# TLNS_driver_board.net
KiCad netlist of a schematic drawn in EAGLE
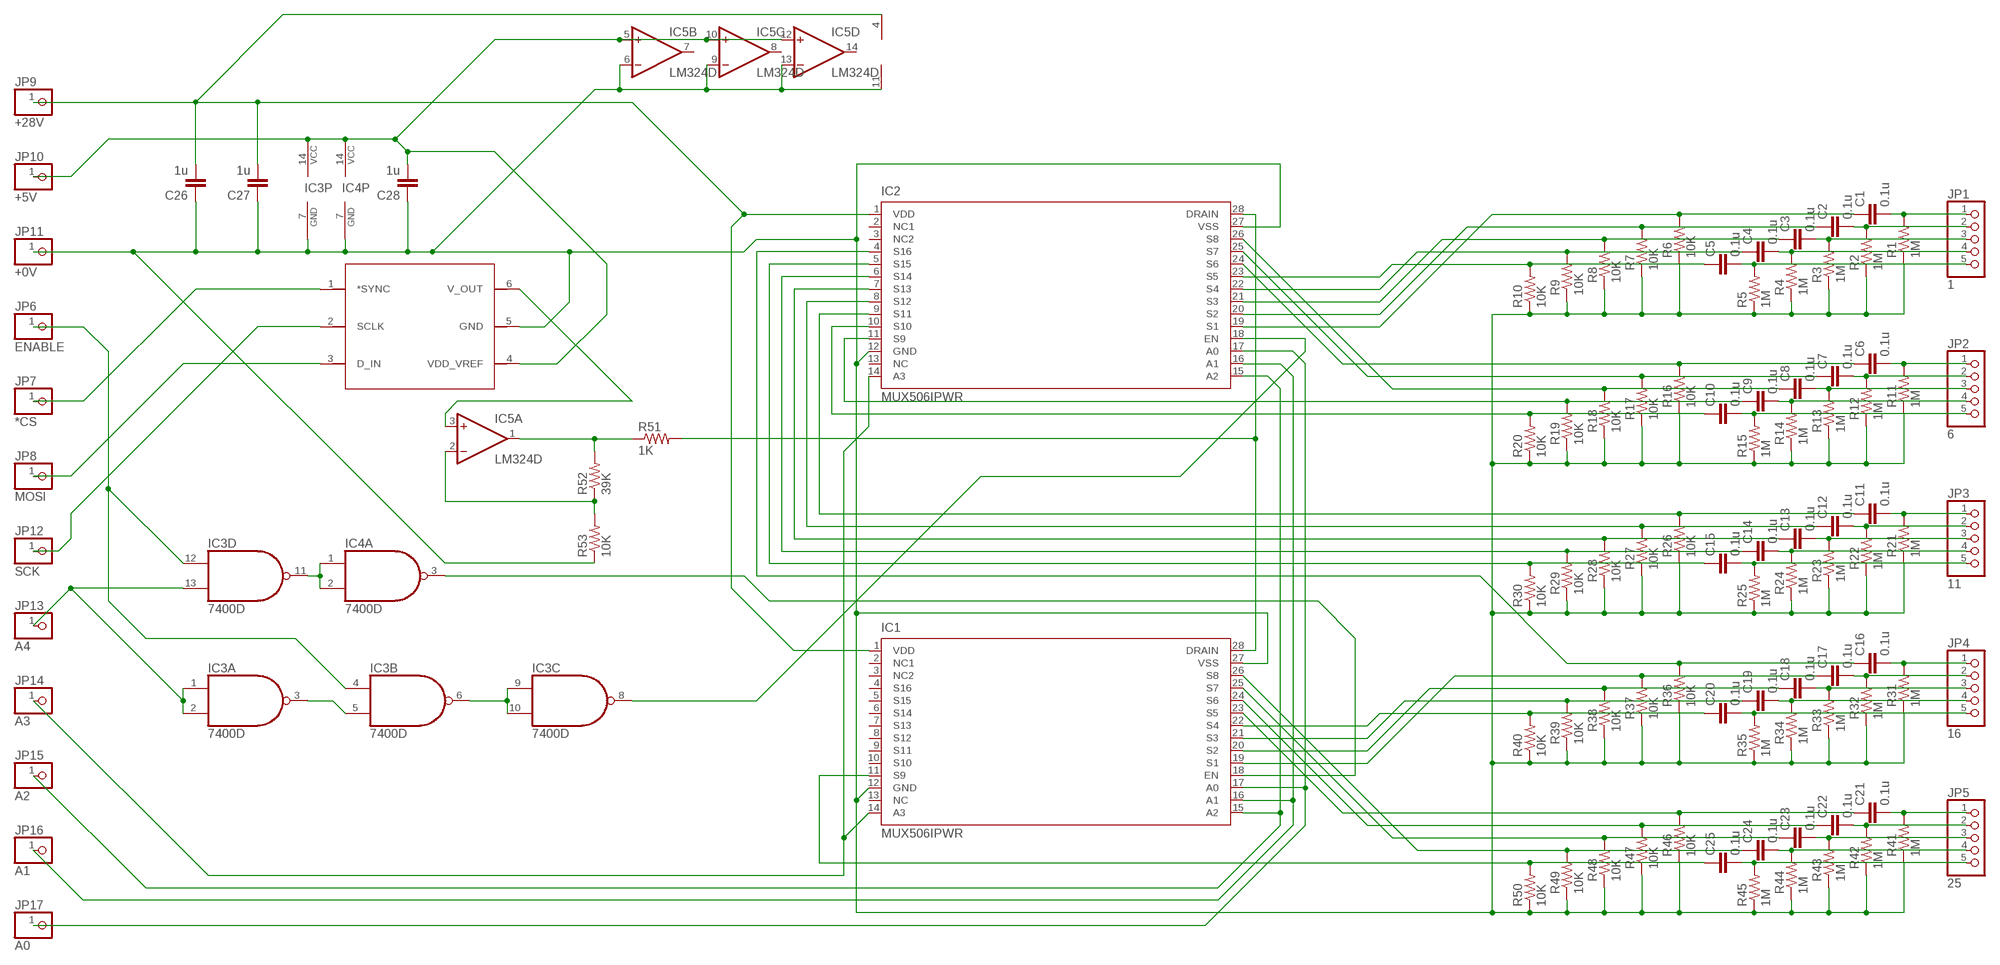
[diagram p0: schematic, sheet 1]

(export (version "E")
  (design (tool "Eeschema 10.0.6"))
  (components
    (comp (ref "C1")
      (value "0.1u")
      (footprint "eagle-import:C0603K")
      (libsource (lib "eagle-import") (part "C-EUC0603K"))
    )
    (comp (ref "C2")
      (value "0.1u")
      (footprint "eagle-import:C0603K")
      (libsource (lib "eagle-import") (part "C-EUC0603K"))
    )
    (comp (ref "C3")
      (value "0.1u")
      (footprint "eagle-import:C0603K")
      (libsource (lib "eagle-import") (part "C-EUC0603K"))
    )
    (comp (ref "C4")
      (value "0.1u")
      (footprint "eagle-import:C0603K")
      (libsource (lib "eagle-import") (part "C-EUC0603K"))
    )
    (comp (ref "C5")
      (value "0.1u")
      (footprint "eagle-import:C0603K")
      (libsource (lib "eagle-import") (part "C-EUC0603K"))
    )
    (comp (ref "C6")
      (value "0.1u")
      (footprint "eagle-import:C0603K")
      (libsource (lib "eagle-import") (part "C-EUC0603K"))
    )
    (comp (ref "C7")
      (value "0.1u")
      (footprint "eagle-import:C0603K")
      (libsource (lib "eagle-import") (part "C-EUC0603K"))
    )
    (comp (ref "C8")
      (value "0.1u")
      (footprint "eagle-import:C0603K")
      (libsource (lib "eagle-import") (part "C-EUC0603K"))
    )
    (comp (ref "C9")
      (value "0.1u")
      (footprint "eagle-import:C0603K")
      (libsource (lib "eagle-import") (part "C-EUC0603K"))
    )
    (comp (ref "C10")
      (value "0.1u")
      (footprint "eagle-import:C0603K")
      (libsource (lib "eagle-import") (part "C-EUC0603K"))
    )
    (comp (ref "C11")
      (value "0.1u")
      (footprint "eagle-import:C0603K")
      (libsource (lib "eagle-import") (part "C-EUC0603K"))
    )
    (comp (ref "C12")
      (value "0.1u")
      (footprint "eagle-import:C0603K")
      (libsource (lib "eagle-import") (part "C-EUC0603K"))
    )
    (comp (ref "C13")
      (value "0.1u")
      (footprint "eagle-import:C0603K")
      (libsource (lib "eagle-import") (part "C-EUC0603K"))
    )
    (comp (ref "C14")
      (value "0.1u")
      (footprint "eagle-import:C0603K")
      (libsource (lib "eagle-import") (part "C-EUC0603K"))
    )
    (comp (ref "C15")
      (value "0.1u")
      (footprint "eagle-import:C0603K")
      (libsource (lib "eagle-import") (part "C-EUC0603K"))
    )
    (comp (ref "C16")
      (value "0.1u")
      (footprint "eagle-import:C0603K")
      (libsource (lib "eagle-import") (part "C-EUC0603K"))
    )
    (comp (ref "C17")
      (value "0.1u")
      (footprint "eagle-import:C0603K")
      (libsource (lib "eagle-import") (part "C-EUC0603K"))
    )
    (comp (ref "C18")
      (value "0.1u")
      (footprint "eagle-import:C0603K")
      (libsource (lib "eagle-import") (part "C-EUC0603K"))
    )
    (comp (ref "C19")
      (value "0.1u")
      (footprint "eagle-import:C0603K")
      (libsource (lib "eagle-import") (part "C-EUC0603K"))
    )
    (comp (ref "C20")
      (value "0.1u")
      (footprint "eagle-import:C0603K")
      (libsource (lib "eagle-import") (part "C-EUC0603K"))
    )
    (comp (ref "C21")
      (value "0.1u")
      (footprint "eagle-import:C0603K")
      (libsource (lib "eagle-import") (part "C-EUC0603K"))
    )
    (comp (ref "C22")
      (value "0.1u")
      (footprint "eagle-import:C0603K")
      (libsource (lib "eagle-import") (part "C-EUC0603K"))
    )
    (comp (ref "C23")
      (value "0.1u")
      (footprint "eagle-import:C0603K")
      (libsource (lib "eagle-import") (part "C-EUC0603K"))
    )
    (comp (ref "C24")
      (value "0.1u")
      (footprint "eagle-import:C0603K")
      (libsource (lib "eagle-import") (part "C-EUC0603K"))
    )
    (comp (ref "C25")
      (value "0.1u")
      (footprint "eagle-import:C0603K")
      (libsource (lib "eagle-import") (part "C-EUC0603K"))
    )
    (comp (ref "C26")
      (value "1u")
      (footprint "eagle-import:C0603K")
      (libsource (lib "eagle-import") (part "C-EUC0603K"))
    )
    (comp (ref "C27")
      (value "1u")
      (footprint "eagle-import:C0603K")
      (libsource (lib "eagle-import") (part "C-EUC0603K"))
    )
    (comp (ref "C28")
      (value "1u")
      (footprint "eagle-import:C0603K")
      (libsource (lib "eagle-import") (part "C-EUC0603K"))
    )
    (comp (ref "IC1")
      (value "MUX506IPWR")
      (footprint "eagle-import:SO28W")
      (fields (field (name "MF") "MICROCHIP") (field (name "MPN") "PIC18F2550-I/SO"))
      (libsource (lib "eagle-import") (part "MUX506IPWRW550"))
    )
    (comp (ref "IC2")
      (value "MUX506IPWR")
      (footprint "eagle-import:SO28W")
      (fields (field (name "MF") "MICROCHIP") (field (name "MPN") "PIC18F2550-I/SO"))
      (libsource (lib "eagle-import") (part "MUX506IPWRW550"))
    )
    (comp (ref "IC3")
      (value "7400D")
      (footprint "eagle-import:SO14")
      (libsource (lib "eagle-import") (part "7400D"))
    )
    (comp (ref "IC4")
      (value "7400D")
      (footprint "eagle-import:SO14")
      (libsource (lib "eagle-import") (part "7400D"))
    )
    (comp (ref "IC5")
      (value "LM324D")
      (footprint "eagle-import:SO14")
      (libsource (lib "eagle-import") (part "LM324D"))
    )
    (comp (ref "JP1")
      (value "1")
      (footprint "eagle-import:1X05")
      (libsource (lib "eagle-import") (part "PINHD-1X5"))
    )
    (comp (ref "JP2")
      (value "6")
      (footprint "eagle-import:1X05")
      (libsource (lib "eagle-import") (part "PINHD-1X5"))
    )
    (comp (ref "JP3")
      (value "11")
      (footprint "eagle-import:1X05")
      (libsource (lib "eagle-import") (part "PINHD-1X5"))
    )
    (comp (ref "JP4")
      (value "16")
      (footprint "eagle-import:1X05")
      (libsource (lib "eagle-import") (part "PINHD-1X5"))
    )
    (comp (ref "JP5")
      (value "25")
      (footprint "eagle-import:1X05")
      (libsource (lib "eagle-import") (part "PINHD-1X5"))
    )
    (comp (ref "JP6")
      (value "ENABLE")
      (footprint "eagle-import:1X01")
      (libsource (lib "eagle-import") (part "PINHD-1X1"))
    )
    (comp (ref "JP7")
      (value "*CS")
      (footprint "eagle-import:1X01")
      (libsource (lib "eagle-import") (part "PINHD-1X1"))
    )
    (comp (ref "JP8")
      (value "MOSI")
      (footprint "eagle-import:1X01")
      (libsource (lib "eagle-import") (part "PINHD-1X1"))
    )
    (comp (ref "JP9")
      (value "+28V")
      (footprint "eagle-import:1X01")
      (libsource (lib "eagle-import") (part "PINHD-1X1"))
    )
    (comp (ref "JP10")
      (value "+5V")
      (footprint "eagle-import:1X01")
      (libsource (lib "eagle-import") (part "PINHD-1X1"))
    )
    (comp (ref "JP11")
      (value "+0V")
      (footprint "eagle-import:1X01")
      (libsource (lib "eagle-import") (part "PINHD-1X1"))
    )
    (comp (ref "JP12")
      (value "SCK")
      (footprint "eagle-import:1X01")
      (libsource (lib "eagle-import") (part "PINHD-1X1"))
    )
    (comp (ref "JP13")
      (value "A4")
      (footprint "eagle-import:1X01")
      (libsource (lib "eagle-import") (part "PINHD-1X1"))
    )
    (comp (ref "JP14")
      (value "A3")
      (footprint "eagle-import:1X01")
      (libsource (lib "eagle-import") (part "PINHD-1X1"))
    )
    (comp (ref "JP15")
      (value "A2")
      (footprint "eagle-import:1X01")
      (libsource (lib "eagle-import") (part "PINHD-1X1"))
    )
    (comp (ref "JP16")
      (value "A1")
      (footprint "eagle-import:1X01")
      (libsource (lib "eagle-import") (part "PINHD-1X1"))
    )
    (comp (ref "JP17")
      (value "A0")
      (footprint "eagle-import:1X01")
      (libsource (lib "eagle-import") (part "PINHD-1X1"))
    )
    (comp (ref "R1")
      (value "1M")
      (footprint "eagle-import:R0603")
      (libsource (lib "eagle-import") (part "R-US_R0603"))
    )
    (comp (ref "R2")
      (value "1M")
      (footprint "eagle-import:R0603")
      (libsource (lib "eagle-import") (part "R-US_R0603"))
    )
    (comp (ref "R3")
      (value "1M")
      (footprint "eagle-import:R0603")
      (libsource (lib "eagle-import") (part "R-US_R0603"))
    )
    (comp (ref "R4")
      (value "1M")
      (footprint "eagle-import:R0603")
      (libsource (lib "eagle-import") (part "R-US_R0603"))
    )
    (comp (ref "R5")
      (value "1M")
      (footprint "eagle-import:R0603")
      (libsource (lib "eagle-import") (part "R-US_R0603"))
    )
    (comp (ref "R6")
      (value "10K")
      (footprint "eagle-import:R0603")
      (libsource (lib "eagle-import") (part "R-US_R0603"))
    )
    (comp (ref "R7")
      (value "10K")
      (footprint "eagle-import:R0603")
      (libsource (lib "eagle-import") (part "R-US_R0603"))
    )
    (comp (ref "R8")
      (value "10K")
      (footprint "eagle-import:R0603")
      (libsource (lib "eagle-import") (part "R-US_R0603"))
    )
    (comp (ref "R9")
      (value "10K")
      (footprint "eagle-import:R0603")
      (libsource (lib "eagle-import") (part "R-US_R0603"))
    )
    (comp (ref "R10")
      (value "10K")
      (footprint "eagle-import:R0603")
      (libsource (lib "eagle-import") (part "R-US_R0603"))
    )
    (comp (ref "R11")
      (value "1M")
      (footprint "eagle-import:R0603")
      (libsource (lib "eagle-import") (part "R-US_R0603"))
    )
    (comp (ref "R12")
      (value "1M")
      (footprint "eagle-import:R0603")
      (libsource (lib "eagle-import") (part "R-US_R0603"))
    )
    (comp (ref "R13")
      (value "1M")
      (footprint "eagle-import:R0603")
      (libsource (lib "eagle-import") (part "R-US_R0603"))
    )
    (comp (ref "R14")
      (value "1M")
      (footprint "eagle-import:R0603")
      (libsource (lib "eagle-import") (part "R-US_R0603"))
    )
    (comp (ref "R15")
      (value "1M")
      (footprint "eagle-import:R0603")
      (libsource (lib "eagle-import") (part "R-US_R0603"))
    )
    (comp (ref "R16")
      (value "10K")
      (footprint "eagle-import:R0603")
      (libsource (lib "eagle-import") (part "R-US_R0603"))
    )
    (comp (ref "R17")
      (value "10K")
      (footprint "eagle-import:R0603")
      (libsource (lib "eagle-import") (part "R-US_R0603"))
    )
    (comp (ref "R18")
      (value "10K")
      (footprint "eagle-import:R0603")
      (libsource (lib "eagle-import") (part "R-US_R0603"))
    )
    (comp (ref "R19")
      (value "10K")
      (footprint "eagle-import:R0603")
      (libsource (lib "eagle-import") (part "R-US_R0603"))
    )
    (comp (ref "R20")
      (value "10K")
      (footprint "eagle-import:R0603")
      (libsource (lib "eagle-import") (part "R-US_R0603"))
    )
    (comp (ref "R21")
      (value "1M")
      (footprint "eagle-import:R0603")
      (libsource (lib "eagle-import") (part "R-US_R0603"))
    )
    (comp (ref "R22")
      (value "1M")
      (footprint "eagle-import:R0603")
      (libsource (lib "eagle-import") (part "R-US_R0603"))
    )
    (comp (ref "R23")
      (value "1M")
      (footprint "eagle-import:R0603")
      (libsource (lib "eagle-import") (part "R-US_R0603"))
    )
    (comp (ref "R24")
      (value "1M")
      (footprint "eagle-import:R0603")
      (libsource (lib "eagle-import") (part "R-US_R0603"))
    )
    (comp (ref "R25")
      (value "1M")
      (footprint "eagle-import:R0603")
      (libsource (lib "eagle-import") (part "R-US_R0603"))
    )
    (comp (ref "R26")
      (value "10K")
      (footprint "eagle-import:R0603")
      (libsource (lib "eagle-import") (part "R-US_R0603"))
    )
    (comp (ref "R27")
      (value "10K")
      (footprint "eagle-import:R0603")
      (libsource (lib "eagle-import") (part "R-US_R0603"))
    )
    (comp (ref "R28")
      (value "10K")
      (footprint "eagle-import:R0603")
      (libsource (lib "eagle-import") (part "R-US_R0603"))
    )
    (comp (ref "R29")
      (value "10K")
      (footprint "eagle-import:R0603")
      (libsource (lib "eagle-import") (part "R-US_R0603"))
    )
    (comp (ref "R30")
      (value "10K")
      (footprint "eagle-import:R0603")
      (libsource (lib "eagle-import") (part "R-US_R0603"))
    )
    (comp (ref "R31")
      (value "1M")
      (footprint "eagle-import:R0603")
      (libsource (lib "eagle-import") (part "R-US_R0603"))
    )
    (comp (ref "R32")
      (value "1M")
      (footprint "eagle-import:R0603")
      (libsource (lib "eagle-import") (part "R-US_R0603"))
    )
    (comp (ref "R33")
      (value "1M")
      (footprint "eagle-import:R0603")
      (libsource (lib "eagle-import") (part "R-US_R0603"))
    )
    (comp (ref "R34")
      (value "1M")
      (footprint "eagle-import:R0603")
      (libsource (lib "eagle-import") (part "R-US_R0603"))
    )
    (comp (ref "R35")
      (value "1M")
      (footprint "eagle-import:R0603")
      (libsource (lib "eagle-import") (part "R-US_R0603"))
    )
    (comp (ref "R36")
      (value "10K")
      (footprint "eagle-import:R0603")
      (libsource (lib "eagle-import") (part "R-US_R0603"))
    )
    (comp (ref "R37")
      (value "10K")
      (footprint "eagle-import:R0603")
      (libsource (lib "eagle-import") (part "R-US_R0603"))
    )
    (comp (ref "R38")
      (value "10K")
      (footprint "eagle-import:R0603")
      (libsource (lib "eagle-import") (part "R-US_R0603"))
    )
    (comp (ref "R39")
      (value "10K")
      (footprint "eagle-import:R0603")
      (libsource (lib "eagle-import") (part "R-US_R0603"))
    )
    (comp (ref "R40")
      (value "10K")
      (footprint "eagle-import:R0603")
      (libsource (lib "eagle-import") (part "R-US_R0603"))
    )
    (comp (ref "R41")
      (value "1M")
      (footprint "eagle-import:R0603")
      (libsource (lib "eagle-import") (part "R-US_R0603"))
    )
    (comp (ref "R42")
      (value "1M")
      (footprint "eagle-import:R0603")
      (libsource (lib "eagle-import") (part "R-US_R0603"))
    )
    (comp (ref "R43")
      (value "1M")
      (footprint "eagle-import:R0603")
      (libsource (lib "eagle-import") (part "R-US_R0603"))
    )
    (comp (ref "R44")
      (value "1M")
      (footprint "eagle-import:R0603")
      (libsource (lib "eagle-import") (part "R-US_R0603"))
    )
    (comp (ref "R45")
      (value "1M")
      (footprint "eagle-import:R0603")
      (libsource (lib "eagle-import") (part "R-US_R0603"))
    )
    (comp (ref "R46")
      (value "10K")
      (footprint "eagle-import:R0603")
      (libsource (lib "eagle-import") (part "R-US_R0603"))
    )
    (comp (ref "R47")
      (value "10K")
      (footprint "eagle-import:R0603")
      (libsource (lib "eagle-import") (part "R-US_R0603"))
    )
    (comp (ref "R48")
      (value "10K")
      (footprint "eagle-import:R0603")
      (libsource (lib "eagle-import") (part "R-US_R0603"))
    )
    (comp (ref "R49")
      (value "10K")
      (footprint "eagle-import:R0603")
      (libsource (lib "eagle-import") (part "R-US_R0603"))
    )
    (comp (ref "R50")
      (value "10K")
      (footprint "eagle-import:R0603")
      (libsource (lib "eagle-import") (part "R-US_R0603"))
    )
    (comp (ref "R51")
      (value "1K")
      (footprint "eagle-import:R1206")
      (libsource (lib "eagle-import") (part "R-US_R1206"))
    )
    (comp (ref "R52")
      (value "39K")
      (footprint "eagle-import:R0603")
      (libsource (lib "eagle-import") (part "R-US_R0603"))
    )
    (comp (ref "R53")
      (value "10K")
      (footprint "eagle-import:R0603")
      (libsource (lib "eagle-import") (part "R-US_R0603"))
    )
    (comp (ref "U$1")
      (value "DAC7311")
      (footprint "eagle-import:SC70-6")
      (libsource (lib "eagle-import") (part "DAC7311"))
    )
  )
  (nets
    (net (code "1") (name "/S12") (class "Default")
      (node (ref "IC1") (pin "8") (pinfunction "S12_8") (pintype "power_in"))
    )
    (net (code "2") (name "Net-(C1-Pad2)") (class "Default")
      (node (ref "C1") (pin "2") (pinfunction "2_2") (pintype "passive"))
      (node (ref "JP1") (pin "1") (pinfunction "1_1") (pintype "passive"))
      (node (ref "R1") (pin "2") (pinfunction "2_2") (pintype "passive"))
    )
    (net (code "3") (name "Net-(C2-Pad2)") (class "Default")
      (node (ref "C2") (pin "2") (pinfunction "2_2") (pintype "passive"))
      (node (ref "JP1") (pin "2") (pinfunction "2_2") (pintype "passive"))
      (node (ref "R2") (pin "2") (pinfunction "2_2") (pintype "passive"))
    )
    (net (code "4") (name "Net-(C3-Pad2)") (class "Default")
      (node (ref "C3") (pin "2") (pinfunction "2_2") (pintype "passive"))
      (node (ref "JP1") (pin "3") (pinfunction "3_3") (pintype "passive"))
      (node (ref "R3") (pin "2") (pinfunction "2_2") (pintype "passive"))
    )
    (net (code "5") (name "Net-(C4-Pad2)") (class "Default")
      (node (ref "C4") (pin "2") (pinfunction "2_2") (pintype "passive"))
      (node (ref "JP1") (pin "4") (pinfunction "4_4") (pintype "passive"))
      (node (ref "R4") (pin "2") (pinfunction "2_2") (pintype "passive"))
    )
    (net (code "6") (name "Net-(C5-Pad2)") (class "Default")
      (node (ref "C5") (pin "2") (pinfunction "2_2") (pintype "passive"))
      (node (ref "JP1") (pin "5") (pinfunction "5_5") (pintype "passive"))
      (node (ref "R5") (pin "2") (pinfunction "2_2") (pintype "passive"))
    )
    (net (code "7") (name "Net-(C6-Pad2)") (class "Default")
      (node (ref "C6") (pin "2") (pinfunction "2_2") (pintype "passive"))
      (node (ref "JP2") (pin "1") (pinfunction "1_1") (pintype "passive"))
      (node (ref "R11") (pin "2") (pinfunction "2_2") (pintype "passive"))
    )
    (net (code "8") (name "Net-(C7-Pad2)") (class "Default")
      (node (ref "C7") (pin "2") (pinfunction "2_2") (pintype "passive"))
      (node (ref "JP2") (pin "2") (pinfunction "2_2") (pintype "passive"))
      (node (ref "R12") (pin "2") (pinfunction "2_2") (pintype "passive"))
    )
    (net (code "9") (name "Net-(C8-Pad2)") (class "Default")
      (node (ref "C8") (pin "2") (pinfunction "2_2") (pintype "passive"))
      (node (ref "JP2") (pin "3") (pinfunction "3_3") (pintype "passive"))
      (node (ref "R13") (pin "2") (pinfunction "2_2") (pintype "passive"))
    )
    (net (code "10") (name "Net-(C9-Pad2)") (class "Default")
      (node (ref "C9") (pin "2") (pinfunction "2_2") (pintype "passive"))
      (node (ref "JP2") (pin "4") (pinfunction "4_4") (pintype "passive"))
      (node (ref "R14") (pin "2") (pinfunction "2_2") (pintype "passive"))
    )
    (net (code "11") (name "Net-(C10-Pad2)") (class "Default")
      (node (ref "C10") (pin "2") (pinfunction "2_2") (pintype "passive"))
      (node (ref "JP2") (pin "5") (pinfunction "5_5") (pintype "passive"))
      (node (ref "R15") (pin "2") (pinfunction "2_2") (pintype "passive"))
    )
    (net (code "12") (name "Net-(C11-Pad2)") (class "Default")
      (node (ref "C11") (pin "2") (pinfunction "2_2") (pintype "passive"))
      (node (ref "JP3") (pin "1") (pinfunction "1_1") (pintype "passive"))
      (node (ref "R21") (pin "2") (pinfunction "2_2") (pintype "passive"))
    )
    (net (code "13") (name "Net-(C12-Pad2)") (class "Default")
      (node (ref "C12") (pin "2") (pinfunction "2_2") (pintype "passive"))
      (node (ref "JP3") (pin "2") (pinfunction "2_2") (pintype "passive"))
      (node (ref "R22") (pin "2") (pinfunction "2_2") (pintype "passive"))
    )
    (net (code "14") (name "Net-(C13-Pad2)") (class "Default")
      (node (ref "C13") (pin "2") (pinfunction "2_2") (pintype "passive"))
      (node (ref "JP3") (pin "3") (pinfunction "3_3") (pintype "passive"))
      (node (ref "R23") (pin "2") (pinfunction "2_2") (pintype "passive"))
    )
    (net (code "15") (name "Net-(C14-Pad2)") (class "Default")
      (node (ref "C14") (pin "2") (pinfunction "2_2") (pintype "passive"))
      (node (ref "JP3") (pin "4") (pinfunction "4_4") (pintype "passive"))
      (node (ref "R24") (pin "2") (pinfunction "2_2") (pintype "passive"))
    )
    (net (code "16") (name "Net-(C15-Pad2)") (class "Default")
      (node (ref "C15") (pin "2") (pinfunction "2_2") (pintype "passive"))
      (node (ref "JP3") (pin "5") (pinfunction "5_5") (pintype "passive"))
      (node (ref "R25") (pin "2") (pinfunction "2_2") (pintype "passive"))
    )
    (net (code "17") (name "Net-(C16-Pad2)") (class "Default")
      (node (ref "C16") (pin "2") (pinfunction "2_2") (pintype "passive"))
      (node (ref "JP4") (pin "1") (pinfunction "1_1") (pintype "passive"))
      (node (ref "R31") (pin "2") (pinfunction "2_2") (pintype "passive"))
    )
    (net (code "18") (name "Net-(C17-Pad2)") (class "Default")
      (node (ref "C17") (pin "2") (pinfunction "2_2") (pintype "passive"))
      (node (ref "JP4") (pin "2") (pinfunction "2_2") (pintype "passive"))
      (node (ref "R32") (pin "2") (pinfunction "2_2") (pintype "passive"))
    )
    (net (code "19") (name "Net-(C18-Pad2)") (class "Default")
      (node (ref "C18") (pin "2") (pinfunction "2_2") (pintype "passive"))
      (node (ref "JP4") (pin "3") (pinfunction "3_3") (pintype "passive"))
      (node (ref "R33") (pin "2") (pinfunction "2_2") (pintype "passive"))
    )
    (net (code "20") (name "Net-(C19-Pad2)") (class "Default")
      (node (ref "C19") (pin "2") (pinfunction "2_2") (pintype "passive"))
      (node (ref "JP4") (pin "4") (pinfunction "4_4") (pintype "passive"))
      (node (ref "R34") (pin "2") (pinfunction "2_2") (pintype "passive"))
    )
    (net (code "21") (name "Net-(C20-Pad2)") (class "Default")
      (node (ref "C20") (pin "2") (pinfunction "2_2") (pintype "passive"))
      (node (ref "JP4") (pin "5") (pinfunction "5_5") (pintype "passive"))
      (node (ref "R35") (pin "2") (pinfunction "2_2") (pintype "passive"))
    )
    (net (code "22") (name "Net-(C21-Pad2)") (class "Default")
      (node (ref "C21") (pin "2") (pinfunction "2_2") (pintype "passive"))
      (node (ref "JP5") (pin "1") (pinfunction "1_1") (pintype "passive"))
      (node (ref "R41") (pin "2") (pinfunction "2_2") (pintype "passive"))
    )
    (net (code "23") (name "Net-(C22-Pad2)") (class "Default")
      (node (ref "C22") (pin "2") (pinfunction "2_2") (pintype "passive"))
      (node (ref "JP5") (pin "2") (pinfunction "2_2") (pintype "passive"))
      (node (ref "R42") (pin "2") (pinfunction "2_2") (pintype "passive"))
    )
    (net (code "24") (name "Net-(C23-Pad2)") (class "Default")
      (node (ref "C23") (pin "2") (pinfunction "2_2") (pintype "passive"))
      (node (ref "JP5") (pin "3") (pinfunction "3_3") (pintype "passive"))
      (node (ref "R43") (pin "2") (pinfunction "2_2") (pintype "passive"))
    )
    (net (code "25") (name "Net-(C24-Pad2)") (class "Default")
      (node (ref "C24") (pin "2") (pinfunction "2_2") (pintype "passive"))
      (node (ref "JP5") (pin "4") (pinfunction "4_4") (pintype "passive"))
      (node (ref "R44") (pin "2") (pinfunction "2_2") (pintype "passive"))
    )
    (net (code "26") (name "Net-(C25-Pad2)") (class "Default")
      (node (ref "C25") (pin "2") (pinfunction "2_2") (pintype "passive"))
      (node (ref "JP5") (pin "5") (pinfunction "5_5") (pintype "passive"))
      (node (ref "R45") (pin "2") (pinfunction "2_2") (pintype "passive"))
    )
    (net (code "27") (name "Net-(IC1-A0)") (class "Default")
      (node (ref "IC1") (pin "17") (pinfunction "A0_17") (pintype "bidirectional"))
      (node (ref "IC2") (pin "17") (pinfunction "A0_17") (pintype "bidirectional"))
      (node (ref "JP17") (pin "1") (pinfunction "1_1") (pintype "passive"))
    )
    (net (code "28") (name "Net-(IC1-A1)") (class "Default")
      (node (ref "IC1") (pin "16") (pinfunction "A1_16") (pintype "bidirectional"))
      (node (ref "IC2") (pin "16") (pinfunction "A1_16") (pintype "bidirectional"))
      (node (ref "JP16") (pin "1") (pinfunction "1_1") (pintype "passive"))
    )
    (net (code "29") (name "Net-(IC1-A2)") (class "Default")
      (node (ref "IC1") (pin "15") (pinfunction "A2_15") (pintype "bidirectional"))
      (node (ref "IC2") (pin "15") (pinfunction "A2_15") (pintype "bidirectional"))
      (node (ref "JP15") (pin "1") (pinfunction "1_1") (pintype "passive"))
    )
    (net (code "30") (name "Net-(IC1-A3)") (class "Default")
      (node (ref "IC1") (pin "14") (pinfunction "A3_14") (pintype "bidirectional"))
      (node (ref "IC2") (pin "14") (pinfunction "A3_14") (pintype "bidirectional"))
      (node (ref "JP14") (pin "1") (pinfunction "1_1") (pintype "passive"))
    )
    (net (code "31") (name "Net-(IC1-DRAIN)") (class "Default")
      (node (ref "IC1") (pin "28") (pinfunction "DRAIN_28") (pintype "bidirectional"))
      (node (ref "IC2") (pin "28") (pinfunction "DRAIN_28") (pintype "bidirectional"))
      (node (ref "R51") (pin "2") (pinfunction "2_2") (pintype "passive"))
    )
    (net (code "32") (name "Net-(IC1-EN)") (class "Default")
      (node (ref "IC1") (pin "18") (pinfunction "EN_18") (pintype "bidirectional"))
      (node (ref "IC4") (pin "3") (pinfunction "O_3") (pintype "output"))
    )
    (net (code "33") (name "Net-(IC1-GND)") (class "Default")
      (node (ref "C26") (pin "1") (pinfunction "1_1") (pintype "passive"))
      (node (ref "C27") (pin "1") (pinfunction "1_1") (pintype "passive"))
      (node (ref "C28") (pin "1") (pinfunction "1_1") (pintype "passive"))
      (node (ref "IC1") (pin "12") (pinfunction "GND_12") (pintype "bidirectional"))
      (node (ref "IC1") (pin "27") (pinfunction "VSS_27") (pintype "bidirectional"))
      (node (ref "IC2") (pin "12") (pinfunction "GND_12") (pintype "bidirectional"))
      (node (ref "IC2") (pin "27") (pinfunction "VSS_27") (pintype "bidirectional"))
      (node (ref "IC3") (pin "7") (pinfunction "GND_7") (pintype "power_in"))
      (node (ref "IC4") (pin "7") (pinfunction "GND_7") (pintype "power_in"))
      (node (ref "IC5") (pin "11") (pinfunction "V-_11") (pintype "power_in"))
      (node (ref "IC5") (pin "13") (pinfunction "-IN_13") (pintype "input"))
      (node (ref "IC5") (pin "6") (pinfunction "-IN_6") (pintype "input"))
      (node (ref "IC5") (pin "9") (pinfunction "-IN_9") (pintype "input"))
      (node (ref "JP11") (pin "1") (pinfunction "1_1") (pintype "passive"))
      (node (ref "R1") (pin "1") (pinfunction "1_1") (pintype "passive"))
      (node (ref "R10") (pin "1") (pinfunction "1_1") (pintype "passive"))
      (node (ref "R11") (pin "1") (pinfunction "1_1") (pintype "passive"))
      (node (ref "R12") (pin "1") (pinfunction "1_1") (pintype "passive"))
      (node (ref "R13") (pin "1") (pinfunction "1_1") (pintype "passive"))
      (node (ref "R14") (pin "1") (pinfunction "1_1") (pintype "passive"))
      (node (ref "R15") (pin "1") (pinfunction "1_1") (pintype "passive"))
      (node (ref "R16") (pin "1") (pinfunction "1_1") (pintype "passive"))
      (node (ref "R17") (pin "1") (pinfunction "1_1") (pintype "passive"))
      (node (ref "R18") (pin "1") (pinfunction "1_1") (pintype "passive"))
      (node (ref "R19") (pin "1") (pinfunction "1_1") (pintype "passive"))
      (node (ref "R2") (pin "1") (pinfunction "1_1") (pintype "passive"))
      (node (ref "R20") (pin "1") (pinfunction "1_1") (pintype "passive"))
      (node (ref "R21") (pin "1") (pinfunction "1_1") (pintype "passive"))
      (node (ref "R22") (pin "1") (pinfunction "1_1") (pintype "passive"))
      (node (ref "R23") (pin "1") (pinfunction "1_1") (pintype "passive"))
      (node (ref "R24") (pin "1") (pinfunction "1_1") (pintype "passive"))
      (node (ref "R25") (pin "1") (pinfunction "1_1") (pintype "passive"))
      (node (ref "R26") (pin "1") (pinfunction "1_1") (pintype "passive"))
      (node (ref "R27") (pin "1") (pinfunction "1_1") (pintype "passive"))
      (node (ref "R28") (pin "1") (pinfunction "1_1") (pintype "passive"))
      (node (ref "R29") (pin "1") (pinfunction "1_1") (pintype "passive"))
      (node (ref "R3") (pin "1") (pinfunction "1_1") (pintype "passive"))
      (node (ref "R30") (pin "1") (pinfunction "1_1") (pintype "passive"))
      (node (ref "R31") (pin "1") (pinfunction "1_1") (pintype "passive"))
      (node (ref "R32") (pin "1") (pinfunction "1_1") (pintype "passive"))
      (node (ref "R33") (pin "1") (pinfunction "1_1") (pintype "passive"))
      (node (ref "R34") (pin "1") (pinfunction "1_1") (pintype "passive"))
      (node (ref "R35") (pin "1") (pinfunction "1_1") (pintype "passive"))
      (node (ref "R36") (pin "1") (pinfunction "1_1") (pintype "passive"))
      (node (ref "R37") (pin "1") (pinfunction "1_1") (pintype "passive"))
      (node (ref "R38") (pin "1") (pinfunction "1_1") (pintype "passive"))
      (node (ref "R39") (pin "1") (pinfunction "1_1") (pintype "passive"))
      (node (ref "R4") (pin "1") (pinfunction "1_1") (pintype "passive"))
      (node (ref "R40") (pin "1") (pinfunction "1_1") (pintype "passive"))
      (node (ref "R41") (pin "1") (pinfunction "1_1") (pintype "passive"))
      (node (ref "R42") (pin "1") (pinfunction "1_1") (pintype "passive"))
      (node (ref "R43") (pin "1") (pinfunction "1_1") (pintype "passive"))
      (node (ref "R44") (pin "1") (pinfunction "1_1") (pintype "passive"))
      (node (ref "R45") (pin "1") (pinfunction "1_1") (pintype "passive"))
      (node (ref "R46") (pin "1") (pinfunction "1_1") (pintype "passive"))
      (node (ref "R47") (pin "1") (pinfunction "1_1") (pintype "passive"))
      (node (ref "R48") (pin "1") (pinfunction "1_1") (pintype "passive"))
      (node (ref "R49") (pin "1") (pinfunction "1_1") (pintype "passive"))
      (node (ref "R5") (pin "1") (pinfunction "1_1") (pintype "passive"))
      (node (ref "R50") (pin "1") (pinfunction "1_1") (pintype "passive"))
      (node (ref "R53") (pin "1") (pinfunction "1_1") (pintype "passive"))
      (node (ref "R6") (pin "1") (pinfunction "1_1") (pintype "passive"))
      (node (ref "R7") (pin "1") (pinfunction "1_1") (pintype "passive"))
      (node (ref "R8") (pin "1") (pinfunction "1_1") (pintype "passive"))
      (node (ref "R9") (pin "1") (pinfunction "1_1") (pintype "passive"))
      (node (ref "U$1") (pin "5") (pinfunction "GND_5") (pintype "bidirectional"))
    )
    (net (code "34") (name "Net-(IC1-S1)") (class "Default")
      (node (ref "C17") (pin "1") (pinfunction "1_1") (pintype "passive"))
      (node (ref "IC1") (pin "19") (pinfunction "S1_19") (pintype "power_in"))
      (node (ref "R37") (pin "2") (pinfunction "2_2") (pintype "passive"))
    )
    (net (code "35") (name "Net-(IC1-S2)") (class "Default")
      (node (ref "C18") (pin "1") (pinfunction "1_1") (pintype "passive"))
      (node (ref "IC1") (pin "20") (pinfunction "S2_20") (pintype "power_in"))
      (node (ref "R38") (pin "2") (pinfunction "2_2") (pintype "passive"))
    )
    (net (code "36") (name "Net-(IC1-S3)") (class "Default")
      (node (ref "C19") (pin "1") (pinfunction "1_1") (pintype "passive"))
      (node (ref "IC1") (pin "21") (pinfunction "S3_21") (pintype "bidirectional"))
      (node (ref "R39") (pin "2") (pinfunction "2_2") (pintype "passive"))
    )
    (net (code "37") (name "Net-(IC1-S4)") (class "Default")
      (node (ref "C20") (pin "1") (pinfunction "1_1") (pintype "passive"))
      (node (ref "IC1") (pin "22") (pinfunction "S4_22") (pintype "bidirectional"))
      (node (ref "R40") (pin "2") (pinfunction "2_2") (pintype "passive"))
    )
    (net (code "38") (name "Net-(IC1-S5)") (class "Default")
      (node (ref "C21") (pin "1") (pinfunction "1_1") (pintype "passive"))
      (node (ref "IC1") (pin "23") (pinfunction "S5_23") (pintype "bidirectional"))
      (node (ref "R46") (pin "2") (pinfunction "2_2") (pintype "passive"))
    )
    (net (code "39") (name "Net-(IC1-S6)") (class "Default")
      (node (ref "C22") (pin "1") (pinfunction "1_1") (pintype "passive"))
      (node (ref "IC1") (pin "24") (pinfunction "S6_24") (pintype "bidirectional"))
      (node (ref "R47") (pin "2") (pinfunction "2_2") (pintype "passive"))
    )
    (net (code "40") (name "Net-(IC1-S7)") (class "Default")
      (node (ref "C23") (pin "1") (pinfunction "1_1") (pintype "passive"))
      (node (ref "IC1") (pin "25") (pinfunction "S7_25") (pintype "bidirectional"))
      (node (ref "R48") (pin "2") (pinfunction "2_2") (pintype "passive"))
    )
    (net (code "41") (name "Net-(IC1-S8)") (class "Default")
      (node (ref "C24") (pin "1") (pinfunction "1_1") (pintype "passive"))
      (node (ref "IC1") (pin "26") (pinfunction "S8_26") (pintype "bidirectional"))
      (node (ref "R49") (pin "2") (pinfunction "2_2") (pintype "passive"))
    )
    (net (code "42") (name "Net-(IC1-S9)") (class "Default")
      (node (ref "C25") (pin "1") (pinfunction "1_1") (pintype "passive"))
      (node (ref "IC1") (pin "11") (pinfunction "S9_11") (pintype "bidirectional"))
      (node (ref "R50") (pin "2") (pinfunction "2_2") (pintype "passive"))
    )
    (net (code "43") (name "Net-(IC1-VDD)") (class "Default")
      (node (ref "C26") (pin "2") (pinfunction "2_2") (pintype "passive"))
      (node (ref "C27") (pin "2") (pinfunction "2_2") (pintype "passive"))
      (node (ref "IC1") (pin "1") (pinfunction "VDD_1") (pintype "input"))
      (node (ref "IC2") (pin "1") (pinfunction "VDD_1") (pintype "input"))
      (node (ref "IC5") (pin "4") (pinfunction "V+_4") (pintype "power_in"))
      (node (ref "JP9") (pin "1") (pinfunction "1_1") (pintype "passive"))
    )
    (net (code "44") (name "Net-(IC2-EN)") (class "Default")
      (node (ref "IC2") (pin "18") (pinfunction "EN_18") (pintype "bidirectional"))
      (node (ref "IC3") (pin "8") (pinfunction "O_8") (pintype "output"))
    )
    (net (code "45") (name "Net-(IC2-S1)") (class "Default")
      (node (ref "C1") (pin "1") (pinfunction "1_1") (pintype "passive"))
      (node (ref "IC2") (pin "19") (pinfunction "S1_19") (pintype "power_in"))
      (node (ref "R6") (pin "2") (pinfunction "2_2") (pintype "passive"))
    )
    (net (code "46") (name "Net-(IC2-S2)") (class "Default")
      (node (ref "C2") (pin "1") (pinfunction "1_1") (pintype "passive"))
      (node (ref "IC2") (pin "20") (pinfunction "S2_20") (pintype "power_in"))
      (node (ref "R7") (pin "2") (pinfunction "2_2") (pintype "passive"))
    )
    (net (code "47") (name "Net-(IC2-S3)") (class "Default")
      (node (ref "C3") (pin "1") (pinfunction "1_1") (pintype "passive"))
      (node (ref "IC2") (pin "21") (pinfunction "S3_21") (pintype "bidirectional"))
      (node (ref "R8") (pin "2") (pinfunction "2_2") (pintype "passive"))
    )
    (net (code "48") (name "Net-(IC2-S4)") (class "Default")
      (node (ref "C4") (pin "1") (pinfunction "1_1") (pintype "passive"))
      (node (ref "IC2") (pin "22") (pinfunction "S4_22") (pintype "bidirectional"))
      (node (ref "R9") (pin "2") (pinfunction "2_2") (pintype "passive"))
    )
    (net (code "49") (name "Net-(IC2-S5)") (class "Default")
      (node (ref "C5") (pin "1") (pinfunction "1_1") (pintype "passive"))
      (node (ref "IC2") (pin "23") (pinfunction "S5_23") (pintype "bidirectional"))
      (node (ref "R10") (pin "2") (pinfunction "2_2") (pintype "passive"))
    )
    (net (code "50") (name "Net-(IC2-S6)") (class "Default")
      (node (ref "C6") (pin "1") (pinfunction "1_1") (pintype "passive"))
      (node (ref "IC2") (pin "24") (pinfunction "S6_24") (pintype "bidirectional"))
      (node (ref "R16") (pin "2") (pinfunction "2_2") (pintype "passive"))
    )
    (net (code "51") (name "Net-(IC2-S7)") (class "Default")
      (node (ref "C7") (pin "1") (pinfunction "1_1") (pintype "passive"))
      (node (ref "IC2") (pin "25") (pinfunction "S7_25") (pintype "bidirectional"))
      (node (ref "R17") (pin "2") (pinfunction "2_2") (pintype "passive"))
    )
    (net (code "52") (name "Net-(IC2-S8)") (class "Default")
      (node (ref "C8") (pin "1") (pinfunction "1_1") (pintype "passive"))
      (node (ref "IC2") (pin "26") (pinfunction "S8_26") (pintype "bidirectional"))
      (node (ref "R18") (pin "2") (pinfunction "2_2") (pintype "passive"))
    )
    (net (code "53") (name "Net-(IC2-S9)") (class "Default")
      (node (ref "C9") (pin "1") (pinfunction "1_1") (pintype "passive"))
      (node (ref "IC2") (pin "11") (pinfunction "S9_11") (pintype "bidirectional"))
      (node (ref "R19") (pin "2") (pinfunction "2_2") (pintype "passive"))
    )
    (net (code "54") (name "Net-(IC2-S10)") (class "Default")
      (node (ref "C10") (pin "1") (pinfunction "1_1") (pintype "passive"))
      (node (ref "IC2") (pin "10") (pinfunction "S10_10") (pintype "output"))
      (node (ref "R20") (pin "2") (pinfunction "2_2") (pintype "passive"))
    )
    (net (code "55") (name "Net-(IC2-S11)") (class "Default")
      (node (ref "C11") (pin "1") (pinfunction "1_1") (pintype "passive"))
      (node (ref "IC2") (pin "9") (pinfunction "S11_9") (pintype "input"))
      (node (ref "R26") (pin "2") (pinfunction "2_2") (pintype "passive"))
    )
    (net (code "56") (name "Net-(IC2-S12)") (class "Default")
      (node (ref "C12") (pin "1") (pinfunction "1_1") (pintype "passive"))
      (node (ref "IC2") (pin "8") (pinfunction "S12_8") (pintype "power_in"))
      (node (ref "R27") (pin "2") (pinfunction "2_2") (pintype "passive"))
    )
    (net (code "57") (name "Net-(IC2-S13)") (class "Default")
      (node (ref "C13") (pin "1") (pinfunction "1_1") (pintype "passive"))
      (node (ref "IC2") (pin "7") (pinfunction "S13_7") (pintype "bidirectional"))
      (node (ref "R28") (pin "2") (pinfunction "2_2") (pintype "passive"))
    )
    (net (code "58") (name "Net-(IC2-S14)") (class "Default")
      (node (ref "C14") (pin "1") (pinfunction "1_1") (pintype "passive"))
      (node (ref "IC2") (pin "6") (pinfunction "S14_6") (pintype "bidirectional"))
      (node (ref "R29") (pin "2") (pinfunction "2_2") (pintype "passive"))
    )
    (net (code "59") (name "Net-(IC2-S15)") (class "Default")
      (node (ref "C15") (pin "1") (pinfunction "1_1") (pintype "passive"))
      (node (ref "IC2") (pin "5") (pinfunction "S15_5") (pintype "bidirectional"))
      (node (ref "R30") (pin "2") (pinfunction "2_2") (pintype "passive"))
    )
    (net (code "60") (name "Net-(IC2-S16)") (class "Default")
      (node (ref "C16") (pin "1") (pinfunction "1_1") (pintype "passive"))
      (node (ref "IC2") (pin "4") (pinfunction "S16_4") (pintype "bidirectional"))
      (node (ref "R36") (pin "2") (pinfunction "2_2") (pintype "passive"))
    )
    (net (code "61") (name "Net-(IC3A-I0)") (class "Default")
      (node (ref "IC3") (pin "1") (pinfunction "I0_1") (pintype "input"))
      (node (ref "IC3") (pin "13") (pinfunction "I1_13") (pintype "input"))
      (node (ref "IC3") (pin "2") (pinfunction "I1_2") (pintype "input"))
      (node (ref "JP13") (pin "1") (pinfunction "1_1") (pintype "passive"))
    )
    (net (code "62") (name "Net-(IC3A-O)") (class "Default")
      (node (ref "IC3") (pin "3") (pinfunction "O_3") (pintype "output"))
      (node (ref "IC3") (pin "5") (pinfunction "I1_5") (pintype "input"))
    )
    (net (code "63") (name "Net-(IC3B-I0)") (class "Default")
      (node (ref "IC3") (pin "12") (pinfunction "I0_12") (pintype "input"))
      (node (ref "IC3") (pin "4") (pinfunction "I0_4") (pintype "input"))
      (node (ref "JP6") (pin "1") (pinfunction "1_1") (pintype "passive"))
    )
    (net (code "64") (name "Net-(IC3B-O)") (class "Default")
      (node (ref "IC3") (pin "10") (pinfunction "I1_10") (pintype "input"))
      (node (ref "IC3") (pin "6") (pinfunction "O_6") (pintype "output"))
      (node (ref "IC3") (pin "9") (pinfunction "I0_9") (pintype "input"))
    )
    (net (code "65") (name "Net-(IC3D-O)") (class "Default")
      (node (ref "IC3") (pin "11") (pinfunction "O_11") (pintype "output"))
      (node (ref "IC4") (pin "1") (pinfunction "I0_1") (pintype "input"))
      (node (ref "IC4") (pin "2") (pinfunction "I1_2") (pintype "input"))
    )
    (net (code "66") (name "Net-(IC3E-VCC)") (class "Default")
      (node (ref "C28") (pin "2") (pinfunction "2_2") (pintype "passive"))
      (node (ref "IC3") (pin "14") (pinfunction "VCC_14") (pintype "power_in"))
      (node (ref "IC4") (pin "14") (pinfunction "VCC_14") (pintype "power_in"))
      (node (ref "IC5") (pin "10") (pinfunction "+IN_10") (pintype "input"))
      (node (ref "IC5") (pin "12") (pinfunction "+IN_12") (pintype "input"))
      (node (ref "IC5") (pin "5") (pinfunction "+IN_5") (pintype "input"))
      (node (ref "JP10") (pin "1") (pinfunction "1_1") (pintype "passive"))
      (node (ref "U$1") (pin "4") (pinfunction "VDD_VREF_4") (pintype "bidirectional"))
    )
    (net (code "67") (name "Net-(IC5A-+IN)") (class "Default")
      (node (ref "IC5") (pin "3") (pinfunction "+IN_3") (pintype "input"))
      (node (ref "U$1") (pin "6") (pinfunction "V_OUT_6") (pintype "bidirectional"))
    )
    (net (code "68") (name "Net-(IC5A--IN)") (class "Default")
      (node (ref "IC5") (pin "2") (pinfunction "-IN_2") (pintype "input"))
      (node (ref "R52") (pin "1") (pinfunction "1_1") (pintype "passive"))
      (node (ref "R53") (pin "2") (pinfunction "2_2") (pintype "passive"))
    )
    (net (code "69") (name "Net-(IC5A-OUT)") (class "Default")
      (node (ref "IC5") (pin "1") (pinfunction "OUT_1") (pintype "output"))
      (node (ref "R51") (pin "1") (pinfunction "1_1") (pintype "passive"))
      (node (ref "R52") (pin "2") (pinfunction "2_2") (pintype "passive"))
    )
    (net (code "70") (name "Net-(U$1-*SYNC)") (class "Default")
      (node (ref "JP7") (pin "1") (pinfunction "1_1") (pintype "passive"))
      (node (ref "U$1") (pin "1") (pinfunction "*SYNC_1") (pintype "bidirectional"))
    )
    (net (code "71") (name "Net-(U$1-D_IN)") (class "Default")
      (node (ref "JP8") (pin "1") (pinfunction "1_1") (pintype "passive"))
      (node (ref "U$1") (pin "3") (pinfunction "D_IN_3") (pintype "bidirectional"))
    )
    (net (code "72") (name "Net-(U$1-SCLK)") (class "Default")
      (node (ref "JP12") (pin "1") (pinfunction "1_1") (pintype "passive"))
      (node (ref "U$1") (pin "2") (pinfunction "SCLK_2") (pintype "bidirectional"))
    )
    (net (code "73") (name "unconnected-(IC1-NC-Pad13)") (class "Default")
      (node (ref "IC1") (pin "13") (pinfunction "NC_13") (pintype "bidirectional"))
    )
    (net (code "74") (name "unconnected-(IC1-NC1-Pad2)") (class "Default")
      (node (ref "IC1") (pin "2") (pinfunction "NC1_2") (pintype "bidirectional"))
    )
    (net (code "75") (name "unconnected-(IC1-NC2-Pad3)") (class "Default")
      (node (ref "IC1") (pin "3") (pinfunction "NC2_3") (pintype "bidirectional"))
    )
    (net (code "76") (name "unconnected-(IC1-S10-Pad10)") (class "Default")
      (node (ref "IC1") (pin "10") (pinfunction "S10_10") (pintype "output"))
    )
    (net (code "77") (name "unconnected-(IC1-S11-Pad9)") (class "Default")
      (node (ref "IC1") (pin "9") (pinfunction "S11_9") (pintype "input"))
    )
    (net (code "78") (name "unconnected-(IC1-S13-Pad7)") (class "Default")
      (node (ref "IC1") (pin "7") (pinfunction "S13_7") (pintype "bidirectional"))
    )
    (net (code "79") (name "unconnected-(IC1-S14-Pad6)") (class "Default")
      (node (ref "IC1") (pin "6") (pinfunction "S14_6") (pintype "bidirectional"))
    )
    (net (code "80") (name "unconnected-(IC1-S15-Pad5)") (class "Default")
      (node (ref "IC1") (pin "5") (pinfunction "S15_5") (pintype "bidirectional"))
    )
    (net (code "81") (name "unconnected-(IC1-S16-Pad4)") (class "Default")
      (node (ref "IC1") (pin "4") (pinfunction "S16_4") (pintype "bidirectional"))
    )
    (net (code "82") (name "unconnected-(IC2-NC-Pad13)") (class "Default")
      (node (ref "IC2") (pin "13") (pinfunction "NC_13") (pintype "bidirectional"))
    )
    (net (code "83") (name "unconnected-(IC2-NC1-Pad2)") (class "Default")
      (node (ref "IC2") (pin "2") (pinfunction "NC1_2") (pintype "bidirectional"))
    )
    (net (code "84") (name "unconnected-(IC2-NC2-Pad3)") (class "Default")
      (node (ref "IC2") (pin "3") (pinfunction "NC2_3") (pintype "bidirectional"))
    )
    (net (code "85") (name "unconnected-(IC5B-OUT-Pad7)") (class "Default")
      (node (ref "IC5") (pin "7") (pinfunction "OUT_7") (pintype "output"))
    )
    (net (code "86") (name "unconnected-(IC5C-OUT-Pad8)") (class "Default")
      (node (ref "IC5") (pin "8") (pinfunction "OUT_8") (pintype "output"))
    )
    (net (code "87") (name "unconnected-(IC5D-OUT-Pad14)") (class "Default")
      (node (ref "IC5") (pin "14") (pinfunction "OUT_14") (pintype "output"))
    )
  )
)
